# DO_EZO_2.net
KiCad netlist of a schematic drawn in Altium Designer
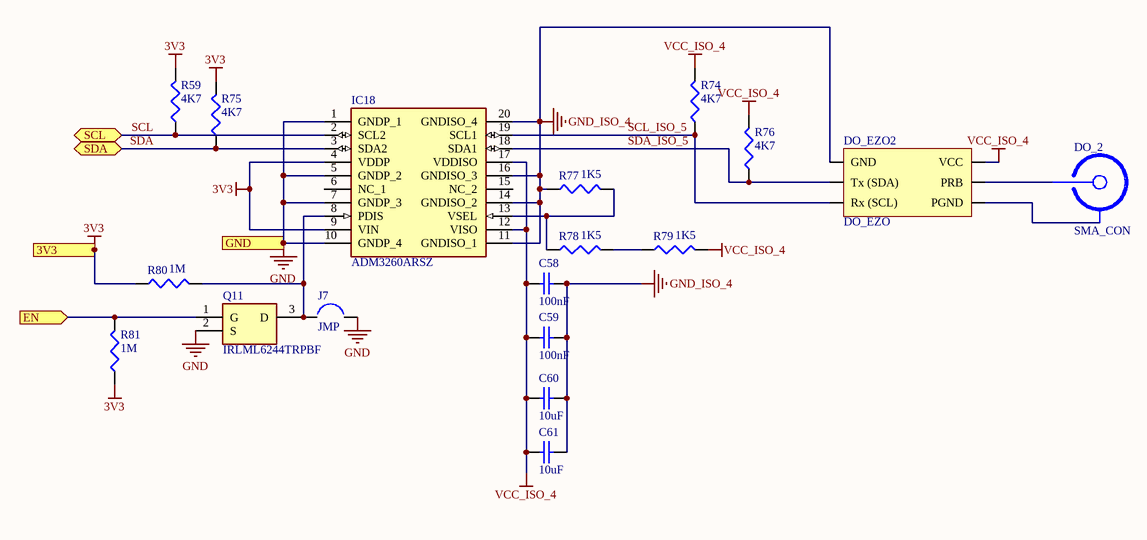
[diagram p0: DO_EZO_2.SchDoc]

(export (version "E")
  (design (tool "Eeschema 10.0.6"))
  (components
    (comp (ref "C58")
      (value "100nF")
      (footprint "1608[0603]")
      (description "Capacitor (Semiconductor SIM Model)")
      (fields (field (name "PUBLISHER") "Altium Limited"))
      (libsource (lib "Miscellaneous Devices") (part "Cap Semi"))
    )
    (comp (ref "C59")
      (value "100nF")
      (footprint "1608[0603]")
      (description "Capacitor (Semiconductor SIM Model)")
      (fields (field (name "PUBLISHER") "Altium Limited"))
      (libsource (lib "Miscellaneous Devices") (part "Cap Semi"))
    )
    (comp (ref "C60")
      (value "10uF")
      (footprint "1608[0603]")
      (description "Capacitor (Semiconductor SIM Model)")
      (fields (field (name "PUBLISHER") "Altium Limited"))
      (libsource (lib "Miscellaneous Devices") (part "Cap Semi"))
    )
    (comp (ref "C61")
      (value "10uF")
      (footprint "1608[0603]")
      (description "Capacitor (Semiconductor SIM Model)")
      (fields (field (name "PUBLISHER") "Altium Limited"))
      (libsource (lib "Miscellaneous Devices") (part "Cap Semi"))
    )
    (comp (ref "DO_2")
      (value "SMA_CON")
      (footprint "SamacSys:PCBSMAFRAHT")
      (description "Connector")
      (fields
        (field (name "MANUFACTURER_PART_NUMBER") "PCB.SMAFRA.HT")
        (field (name "MOUSER PART NUMBER") "960-PCB.SMAFRA.HT")
      )
      (libsource (lib "SamacSys") (part "SMA"))
    )
    (comp (ref "DO_EZO2") (value "DO_EZO") (footprint "DO_EZO") (libsource (lib "SamacSys") (part "DO_EZO")))
    (comp (ref "IC18")
      (value "ADM3260ARSZ")
      (footprint "SOP65P780X200-20N")
      (description "Integrated Circuit")
      (fields
        (field (name "MOUSER PART NUMBER") "584-ADM3260ARSZ")
        (field (name "RS PART NUMBER") "8319113P")
      )
      (libsource (lib "SamacSys") (part "ADM3260ARSZ"))
    )
    (comp (ref "J7") (value "JMP") (footprint "Jumper") (libsource (lib "SamacSys") (part "JMP")))
    (comp (ref "Q11")
      (value "IRLML6244TRPBF")
      (footprint "SOT95P237X112-3N")
      (description "Transistor")
      (fields
        (field (name "MOUSER PART NUMBER") "942-IRLML6244TRPBF")
        (field (name "RS PART NUMBER") "7377228P")
      )
      (libsource (lib "SamacSys") (part "IRLML6244TRPBF"))
    )
    (comp (ref "R59")
      (value "4K7")
      (footprint "J1-0603")
      (description "Resistor")
      (fields (field (name "PUBLISHER") "Altium Limited"))
      (libsource (lib "Miscellaneous Devices") (part "Res3"))
    )
    (comp (ref "R74")
      (value "4K7")
      (footprint "J1-0603")
      (description "Resistor")
      (fields (field (name "PUBLISHER") "Altium Limited"))
      (libsource (lib "Miscellaneous Devices") (part "Res3"))
    )
    (comp (ref "R75")
      (value "4K7")
      (footprint "J1-0603")
      (description "Resistor")
      (fields (field (name "PUBLISHER") "Altium Limited"))
      (libsource (lib "Miscellaneous Devices") (part "Res3"))
    )
    (comp (ref "R76")
      (value "4K7")
      (footprint "J1-0603")
      (description "Resistor")
      (fields (field (name "PUBLISHER") "Altium Limited"))
      (libsource (lib "Miscellaneous Devices") (part "Res3"))
    )
    (comp (ref "R77")
      (value "1K5")
      (footprint "J1-0603")
      (description "Resistor")
      (fields (field (name "PUBLISHER") "Altium Limited"))
      (libsource (lib "Miscellaneous Devices") (part "Res3"))
    )
    (comp (ref "R78")
      (value "1K5")
      (footprint "J1-0603")
      (description "Resistor")
      (fields (field (name "PUBLISHER") "Altium Limited"))
      (libsource (lib "Miscellaneous Devices") (part "Res3"))
    )
    (comp (ref "R79")
      (value "1K5")
      (footprint "J1-0603")
      (description "Resistor")
      (fields (field (name "PUBLISHER") "Altium Limited"))
      (libsource (lib "Miscellaneous Devices") (part "Res3"))
    )
    (comp (ref "R80")
      (value "1M")
      (footprint "J1-0603")
      (description "Resistor")
      (fields (field (name "PUBLISHER") "Altium Limited"))
      (libsource (lib "Miscellaneous Devices") (part "Res3"))
    )
    (comp (ref "R81")
      (value "1M")
      (footprint "J1-0603")
      (description "Resistor")
      (fields (field (name "PUBLISHER") "Altium Limited"))
      (libsource (lib "Miscellaneous Devices") (part "Res3"))
    )
  )
  (nets
    (net (code "1") (name "/EN") (class "Default")
      (node (ref "Q11") (pin "1") (pinfunction "G_1") (pintype "passive"))
      (node (ref "R81") (pin "2") (pinfunction "2_2") (pintype "passive"))
    )
    (net (code "2") (name "/SCL") (class "Default")
      (node (ref "IC18") (pin "2") (pinfunction "SCL2_2") (pintype "bidirectional"))
      (node (ref "R59") (pin "1") (pinfunction "1_1") (pintype "passive"))
    )
    (net (code "3") (name "/SCL_ISO_5") (class "Default")
      (node (ref "DO_EZO2") (pin "3") (pinfunction "Rx_(SCL)_3") (pintype "passive"))
      (node (ref "IC18") (pin "19") (pinfunction "SCL1_19") (pintype "bidirectional"))
      (node (ref "R74") (pin "1") (pinfunction "1_1") (pintype "passive"))
    )
    (net (code "4") (name "/SDA") (class "Default")
      (node (ref "IC18") (pin "3") (pinfunction "SDA2_3") (pintype "bidirectional"))
      (node (ref "R75") (pin "1") (pinfunction "1_1") (pintype "passive"))
    )
    (net (code "5") (name "/SDA_ISO_5") (class "Default")
      (node (ref "DO_EZO2") (pin "2") (pinfunction "Tx_(SDA)_2") (pintype "passive"))
      (node (ref "IC18") (pin "18") (pinfunction "SDA1_18") (pintype "bidirectional"))
      (node (ref "R76") (pin "1") (pinfunction "1_1") (pintype "passive"))
    )
    (net (code "6") (name "3V3") (class "Default")
      (node (ref "IC18") (pin "4") (pinfunction "VDDP_4") (pintype "power_in"))
      (node (ref "IC18") (pin "9") (pinfunction "VIN_9") (pintype "power_in"))
      (node (ref "R59") (pin "2") (pinfunction "2_2") (pintype "passive"))
      (node (ref "R75") (pin "2") (pinfunction "2_2") (pintype "passive"))
      (node (ref "R80") (pin "1") (pinfunction "1_1") (pintype "passive"))
      (node (ref "R81") (pin "1") (pinfunction "1_1") (pintype "passive"))
    )
    (net (code "7") (name "GND") (class "Default")
      (node (ref "IC18") (pin "1") (pinfunction "GNDP_1_1") (pintype "power_in"))
      (node (ref "IC18") (pin "10") (pinfunction "GNDP_4_10") (pintype "power_in"))
      (node (ref "IC18") (pin "5") (pinfunction "GNDP_2_5") (pintype "power_in"))
      (node (ref "IC18") (pin "7") (pinfunction "GNDP_3_7") (pintype "power_in"))
      (node (ref "J7") (pin "2") (pinfunction "2_2") (pintype "passive"))
      (node (ref "Q11") (pin "2") (pinfunction "S_2") (pintype "passive"))
    )
    (net (code "8") (name "GND_ISO_4") (class "Default")
      (node (ref "C58") (pin "2") (pinfunction "2_2") (pintype "passive"))
      (node (ref "C59") (pin "2") (pinfunction "2_2") (pintype "passive"))
      (node (ref "C60") (pin "2") (pinfunction "2_2") (pintype "passive"))
      (node (ref "C61") (pin "2") (pinfunction "2_2") (pintype "passive"))
      (node (ref "DO_EZO2") (pin "1") (pinfunction "GND_1") (pintype "passive"))
      (node (ref "IC18") (pin "11") (pinfunction "GNDISO_1_11") (pintype "power_in"))
      (node (ref "IC18") (pin "14") (pinfunction "GNDISO_2_14") (pintype "power_in"))
      (node (ref "IC18") (pin "16") (pinfunction "GNDISO_3_16") (pintype "power_in"))
      (node (ref "IC18") (pin "20") (pinfunction "GNDISO_4_20") (pintype "power_in"))
      (node (ref "R77") (pin "1") (pinfunction "1_1") (pintype "passive"))
    )
    (net (code "9") (name "Net-(DO_EZO2-PGND)") (class "Default")
      (node (ref "DO_2") (pin "2") (pintype "passive"))
      (node (ref "DO_EZO2") (pin "6") (pinfunction "PGND_6") (pintype "passive"))
    )
    (net (code "10") (name "Net-(DO_EZO2-PRB)") (class "Default")
      (node (ref "DO_2") (pin "1") (pintype "passive"))
      (node (ref "DO_EZO2") (pin "5") (pinfunction "PRB_5") (pintype "passive"))
    )
    (net (code "11") (name "Net-(IC18-PDIS)") (class "Default")
      (node (ref "IC18") (pin "8") (pinfunction "PDIS_8") (pintype "input"))
      (node (ref "J7") (pin "1") (pinfunction "1_1") (pintype "passive"))
      (node (ref "Q11") (pin "3") (pinfunction "D_3") (pintype "passive"))
      (node (ref "R80") (pin "2") (pinfunction "2_2") (pintype "passive"))
    )
    (net (code "12") (name "Net-(IC18-VSEL)") (class "Default")
      (node (ref "IC18") (pin "13") (pinfunction "VSEL_13") (pintype "input"))
      (node (ref "R77") (pin "2") (pinfunction "2_2") (pintype "passive"))
      (node (ref "R78") (pin "1") (pinfunction "1_1") (pintype "passive"))
    )
    (net (code "13") (name "Net-(R78-Pad2)") (class "Default")
      (node (ref "R78") (pin "2") (pinfunction "2_2") (pintype "passive"))
      (node (ref "R79") (pin "1") (pinfunction "1_1") (pintype "passive"))
    )
    (net (code "14") (name "VCC_ISO_4") (class "Default")
      (node (ref "C58") (pin "1") (pinfunction "1_1") (pintype "passive"))
      (node (ref "C59") (pin "1") (pinfunction "1_1") (pintype "passive"))
      (node (ref "C60") (pin "1") (pinfunction "1_1") (pintype "passive"))
      (node (ref "C61") (pin "1") (pinfunction "1_1") (pintype "passive"))
      (node (ref "DO_EZO2") (pin "4") (pinfunction "VCC_4") (pintype "passive"))
      (node (ref "IC18") (pin "12") (pinfunction "VISO_12") (pintype "power_in"))
      (node (ref "IC18") (pin "17") (pinfunction "VDDISO_17") (pintype "power_in"))
      (node (ref "R74") (pin "2") (pinfunction "2_2") (pintype "passive"))
      (node (ref "R76") (pin "2") (pinfunction "2_2") (pintype "passive"))
      (node (ref "R79") (pin "2") (pinfunction "2_2") (pintype "passive"))
    )
    (net (code "15") (name "unconnected-(IC18-NC_1-Pad6)") (class "Default")
      (node (ref "IC18") (pin "6") (pinfunction "NC_1_6") (pintype "passive"))
    )
    (net (code "16") (name "unconnected-(IC18-NC_2-Pad15)") (class "Default")
      (node (ref "IC18") (pin "15") (pinfunction "NC_2_15") (pintype "passive"))
    )
  )
)
